# halfAdder.net
KiCad netlist of a schematic drawn in EAGLE
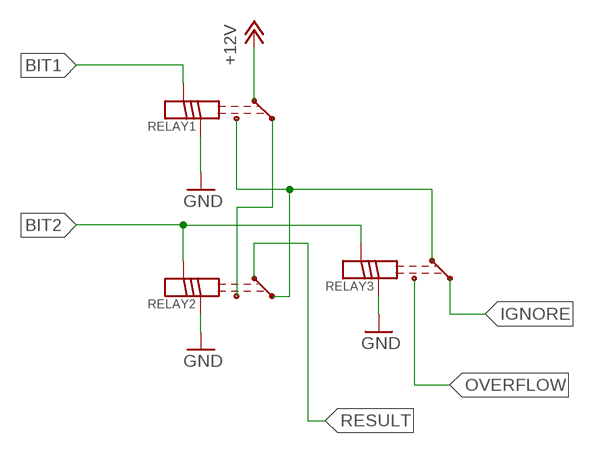
[diagram p0: schematic, sheet 1]

(export (version "E")
  (design (tool "Eeschema 10.0.6"))
  (components
    (comp (ref "RELAY1")
      (value "basicRelay")
      (footprint "eagle-import:RELAY-FINDER-40.51")
      (libsource (lib "eagle-import") (part "RELAY-GENERIC"))
    )
    (comp (ref "RELAY2")
      (value "basicRelay")
      (footprint "eagle-import:RELAY-FINDER-40.51")
      (libsource (lib "eagle-import") (part "RELAY-GENERIC"))
    )
    (comp (ref "RELAY3")
      (value "basicRelay")
      (footprint "eagle-import:RELAY-FINDER-40.51")
      (libsource (lib "eagle-import") (part "RELAY-GENERIC"))
    )
  )
  (nets
    (net (code "1") (name "+12V") (class "Default")
      (node (ref "RELAY1") (pin "CENTER") (pinfunction "CENTER_CENTER") (pintype "bidirectional"))
    )
    (net (code "2") (name "BIT1") (class "Default")
      (node (ref "RELAY1") (pin "N+") (pinfunction "N+_N+") (pintype "bidirectional"))
    )
    (net (code "3") (name "BIT2") (class "Default")
      (node (ref "RELAY2") (pin "N+") (pinfunction "N+_N+") (pintype "bidirectional"))
      (node (ref "RELAY3") (pin "N+") (pinfunction "N+_N+") (pintype "bidirectional"))
    )
    (net (code "4") (name "GND") (class "Default")
      (node (ref "RELAY1") (pin "N-") (pinfunction "N-_N-") (pintype "bidirectional"))
      (node (ref "RELAY2") (pin "N-") (pinfunction "N-_N-") (pintype "bidirectional"))
      (node (ref "RELAY3") (pin "N-") (pinfunction "N-_N-") (pintype "bidirectional"))
    )
    (net (code "5") (name "IGNORE") (class "Default")
      (node (ref "RELAY3") (pin "NCL") (pinfunction "NCL_NCL") (pintype "bidirectional"))
    )
    (net (code "6") (name "Net-(RELAY1-PadNCL)") (class "Default")
      (node (ref "RELAY1") (pin "NCL") (pinfunction "NCL_NCL") (pintype "bidirectional"))
      (node (ref "RELAY2") (pin "NOP") (pinfunction "NOP_NOP") (pintype "bidirectional"))
    )
    (net (code "7") (name "Net-(RELAY1-PadNOP)") (class "Default")
      (node (ref "RELAY1") (pin "NOP") (pinfunction "NOP_NOP") (pintype "bidirectional"))
      (node (ref "RELAY2") (pin "NCL") (pinfunction "NCL_NCL") (pintype "bidirectional"))
      (node (ref "RELAY3") (pin "CENTER") (pinfunction "CENTER_CENTER") (pintype "bidirectional"))
    )
    (net (code "8") (name "OVERFLOW") (class "Default")
      (node (ref "RELAY3") (pin "NOP") (pinfunction "NOP_NOP") (pintype "bidirectional"))
    )
    (net (code "9") (name "RESULT") (class "Default")
      (node (ref "RELAY2") (pin "CENTER") (pinfunction "CENTER_CENTER") (pintype "bidirectional"))
    )
  )
)
